# USB-A.net
KiCad netlist of a schematic drawn in EAGLE
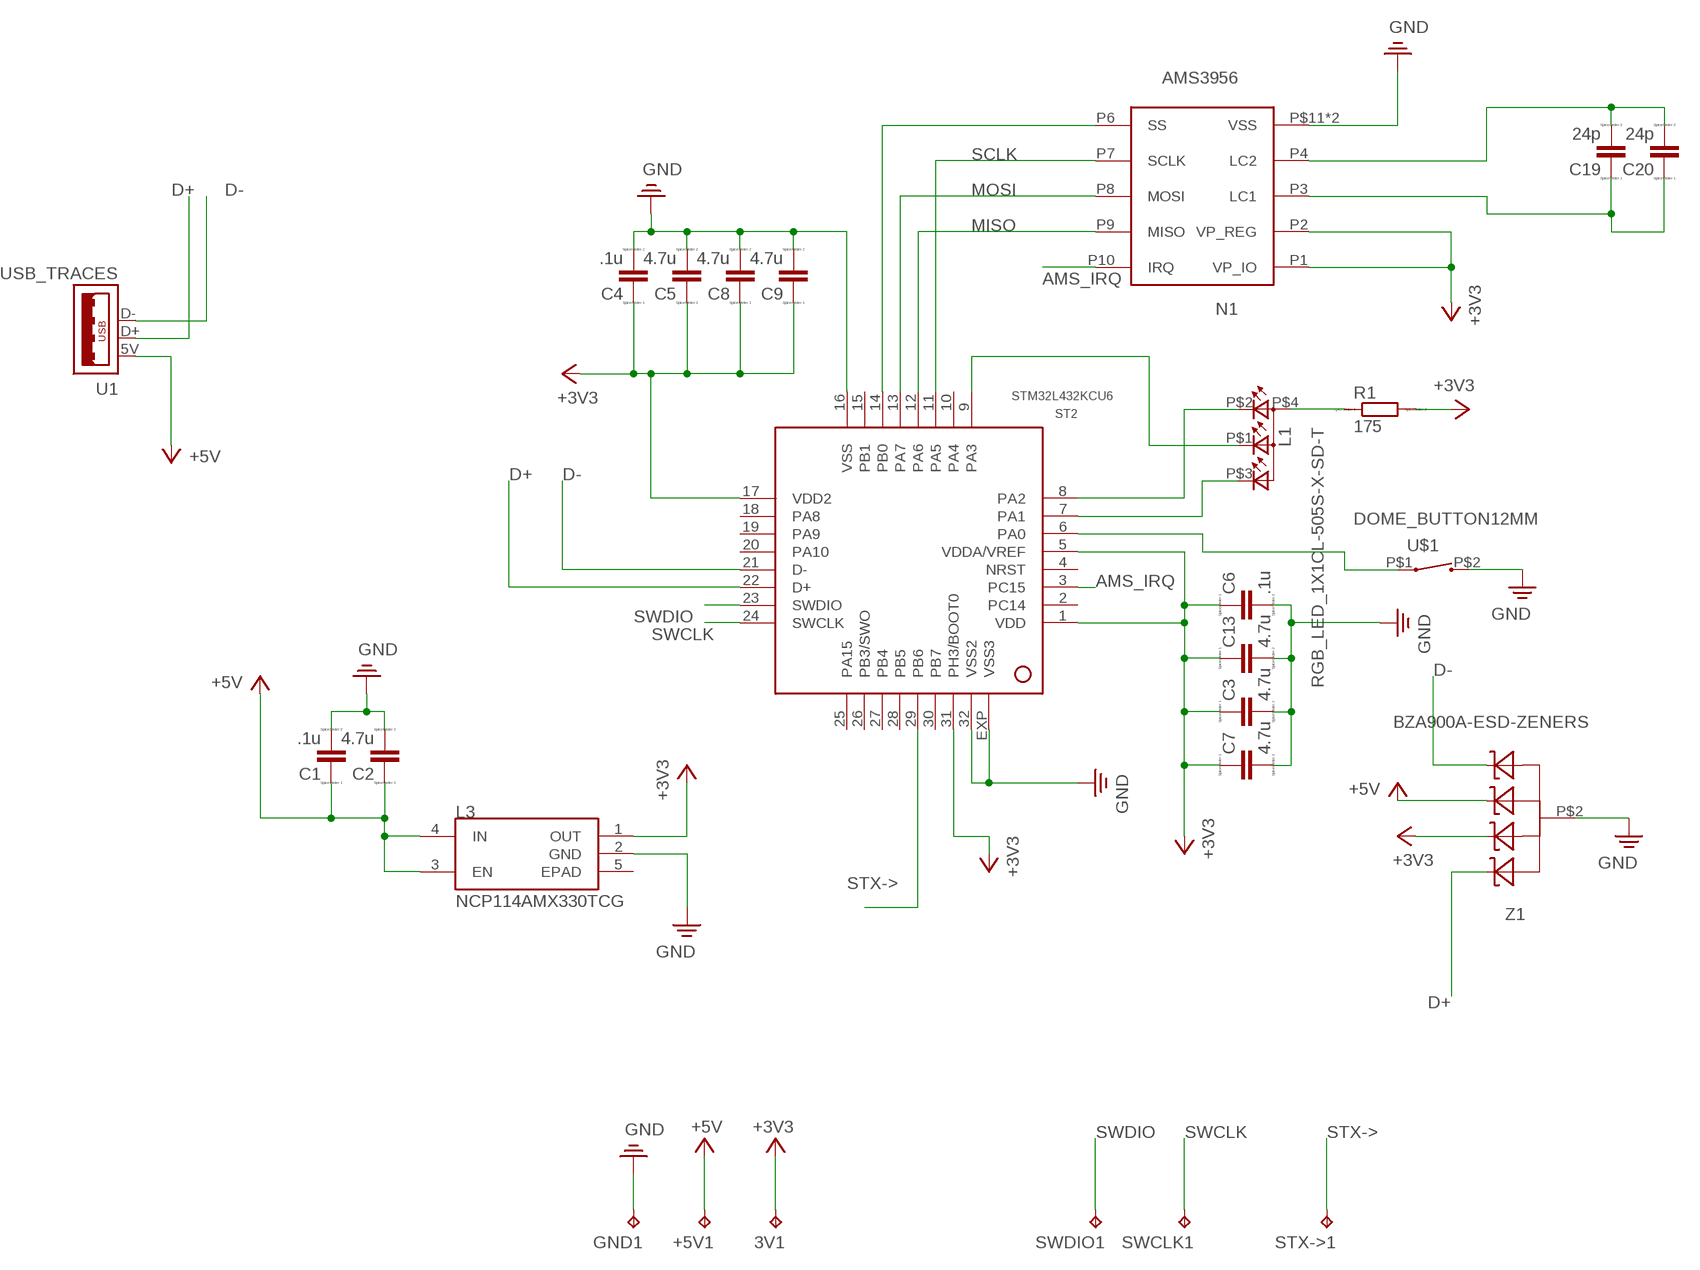
[diagram p0: schematic, sheet 1]

(export (version "E")
  (design (tool "Eeschema 10.0.6"))
  (components
    (comp (ref "+5V1")
      (value "TEST_POINT")
      (footprint "eagle-import:B1,27")
      (libsource (lib "eagle-import") (part "TEST_POINT"))
    )
    (comp (ref "3V1")
      (value "TEST_POINT")
      (footprint "eagle-import:B1,27")
      (libsource (lib "eagle-import") (part "TEST_POINT"))
    )
    (comp (ref "C1")
      (value ".1u")
      (footprint "eagle-import:C0402")
      (libsource (lib "eagle-import") (part "CAPACITOR"))
    )
    (comp (ref "C2")
      (value "4.7u")
      (footprint "eagle-import:C0402")
      (libsource (lib "eagle-import") (part "CAPACITOR"))
    )
    (comp (ref "C3")
      (value "4.7u")
      (footprint "eagle-import:C0402")
      (libsource (lib "eagle-import") (part "CAPACITOR"))
    )
    (comp (ref "C4")
      (value ".1u")
      (footprint "eagle-import:C0402")
      (libsource (lib "eagle-import") (part "CAPACITOR"))
    )
    (comp (ref "C5")
      (value "4.7u")
      (footprint "eagle-import:C0402")
      (libsource (lib "eagle-import") (part "CAPACITOR"))
    )
    (comp (ref "C6")
      (value ".1u")
      (footprint "eagle-import:C0402")
      (libsource (lib "eagle-import") (part "CAPACITOR"))
    )
    (comp (ref "C7")
      (value "4.7u")
      (footprint "eagle-import:C0402")
      (libsource (lib "eagle-import") (part "CAPACITOR"))
    )
    (comp (ref "C8")
      (value "4.7u")
      (footprint "eagle-import:C0402")
      (libsource (lib "eagle-import") (part "CAPACITOR"))
    )
    (comp (ref "C9")
      (value "4.7u")
      (footprint "eagle-import:C0402")
      (libsource (lib "eagle-import") (part "CAPACITOR"))
    )
    (comp (ref "C13")
      (value "4.7u")
      (footprint "eagle-import:C0402")
      (libsource (lib "eagle-import") (part "CAPACITOR"))
    )
    (comp (ref "C19")
      (value "24p")
      (footprint "eagle-import:C0402")
      (libsource (lib "eagle-import") (part "CAPACITOR"))
    )
    (comp (ref "C20")
      (value "24p")
      (footprint "eagle-import:C0402")
      (libsource (lib "eagle-import") (part "CAPACITOR"))
    )
    (comp (ref "GND1")
      (value "TEST_POINT")
      (footprint "eagle-import:B1,27")
      (libsource (lib "eagle-import") (part "TEST_POINT"))
    )
    (comp (ref "L1")
      (value "RGB_LED_1X1CL-505S-X-SD-T")
      (footprint "eagle-import:CL-505S-X-SD-T")
      (libsource (lib "eagle-import") (part "RGB_LED_1X1CL-505S-X-SD-T"))
    )
    (comp (ref "L3")
      (value "NCP114AMX330TCG")
      (footprint "eagle-import:REG_NCP114AMX330TCG")
      (fields (field (name "MF") "ON Semiconductor"))
      (libsource (lib "eagle-import") (part "NCP114AMX330TCG"))
    )
    (comp (ref "N1")
      (value "AMS3956")
      (footprint "eagle-import:MLPD3X3")
      (libsource (lib "eagle-import") (part "AMS3956"))
    )
    (comp (ref "R1")
      (value "175")
      (footprint "eagle-import:R0402")
      (libsource (lib "eagle-import") (part "RESISTOR"))
    )
    (comp (ref "ST2")
      (value "STM32L432KCU6")
      (footprint "eagle-import:QFN32")
      (libsource (lib "eagle-import") (part "STM32L432KCU6"))
    )
    (comp (ref "STX->1")
      (value "TEST_POINT")
      (footprint "eagle-import:B1,27")
      (libsource (lib "eagle-import") (part "TEST_POINT"))
    )
    (comp (ref "SWCLK1")
      (value "TEST_POINT")
      (footprint "eagle-import:B1,27")
      (libsource (lib "eagle-import") (part "TEST_POINT"))
    )
    (comp (ref "SWDIO1")
      (value "TEST_POINT")
      (footprint "eagle-import:B1,27")
      (libsource (lib "eagle-import") (part "TEST_POINT"))
    )
    (comp (ref "U$1")
      (value "DOME_BUTTON12MM")
      (footprint "eagle-import:DOME-BL-12MM")
      (libsource (lib "eagle-import") (part "DOME_BUTTON12MM"))
    )
    (comp (ref "U1")
      (value "USB_TRACES")
      (footprint "eagle-import:USB_TRACES")
      (libsource (lib "eagle-import") (part "USB_TRACES"))
    )
    (comp (ref "Z1")
      (value "BZA900A-ESD-ZENERS")
      (footprint "eagle-import:BZA900A")
      (libsource (lib "eagle-import") (part "BZA900A-ESD-ZENERS"))
    )
  )
  (nets
    (net (code "1") (name "+3V3") (class "Default")
      (node (ref "3V1") (pin "TP") (pinfunction "TP_TP") (pintype "input"))
      (node (ref "C13") (pin "1") (pinfunction "1_1") (pintype "passive"))
      (node (ref "C3") (pin "1") (pinfunction "1_1") (pintype "passive"))
      (node (ref "C4") (pin "1") (pinfunction "1_1") (pintype "passive"))
      (node (ref "C5") (pin "1") (pinfunction "1_1") (pintype "passive"))
      (node (ref "C6") (pin "1") (pinfunction "1_1") (pintype "passive"))
      (node (ref "C7") (pin "1") (pinfunction "1_1") (pintype "passive"))
      (node (ref "C8") (pin "1") (pinfunction "1_1") (pintype "passive"))
      (node (ref "C9") (pin "1") (pinfunction "1_1") (pintype "passive"))
      (node (ref "L3") (pin "1") (pinfunction "OUT_1") (pintype "output"))
      (node (ref "N1") (pin "P1") (pinfunction "VP_IO_P1") (pintype "bidirectional"))
      (node (ref "N1") (pin "P2") (pinfunction "VP_REG_P2") (pintype "bidirectional"))
      (node (ref "R1") (pin "2") (pinfunction "2_2") (pintype "passive"))
      (node (ref "ST2") (pin "1") (pinfunction "VDD_1") (pintype "bidirectional"))
      (node (ref "ST2") (pin "17") (pinfunction "VDD2_17") (pintype "bidirectional"))
      (node (ref "ST2") (pin "31") (pinfunction "PH3/BOOT0_31") (pintype "bidirectional"))
      (node (ref "ST2") (pin "5") (pinfunction "VDDA/VREF_5") (pintype "bidirectional"))
      (node (ref "Z1") (pin "P$5") (pinfunction "C1_P$5") (pintype "passive"))
    )
    (net (code "2") (name "+5V") (class "Default")
      (node (ref "+5V1") (pin "TP") (pinfunction "TP_TP") (pintype "input"))
      (node (ref "C1") (pin "1") (pinfunction "1_1") (pintype "passive"))
      (node (ref "C2") (pin "1") (pinfunction "1_1") (pintype "passive"))
      (node (ref "L3") (pin "3") (pinfunction "EN_3") (pintype "input"))
      (node (ref "L3") (pin "4") (pinfunction "IN_4") (pintype "input"))
      (node (ref "U1") (pin "5V") (pinfunction "1_5V") (pintype "passive"))
      (node (ref "Z1") (pin "P$1") (pinfunction "C_P$1") (pintype "passive"))
    )
    (net (code "3") (name "/AMS_IRQ") (class "Default")
      (node (ref "N1") (pin "P10") (pinfunction "IRQ_P10") (pintype "bidirectional"))
      (node (ref "ST2") (pin "3") (pinfunction "PC15_3") (pintype "bidirectional"))
    )
    (net (code "4") (name "/D+") (class "Default")
      (node (ref "ST2") (pin "22") (pinfunction "D+_22") (pintype "bidirectional"))
      (node (ref "U1") (pin "D+") (pinfunction "2_D+") (pintype "passive"))
      (node (ref "Z1") (pin "P$3") (pinfunction "C3_P$3") (pintype "passive"))
    )
    (net (code "5") (name "/D-") (class "Default")
      (node (ref "ST2") (pin "21") (pinfunction "D-_21") (pintype "bidirectional"))
      (node (ref "U1") (pin "D-") (pinfunction "3_D-") (pintype "passive"))
      (node (ref "Z1") (pin "P$4") (pinfunction "C2_P$4") (pintype "passive"))
    )
    (net (code "6") (name "/MISO") (class "Default")
      (node (ref "N1") (pin "P9") (pinfunction "MISO_P9") (pintype "bidirectional"))
      (node (ref "ST2") (pin "12") (pinfunction "PA6_12") (pintype "bidirectional"))
    )
    (net (code "7") (name "/MOSI") (class "Default")
      (node (ref "N1") (pin "P8") (pinfunction "MOSI_P8") (pintype "bidirectional"))
      (node (ref "ST2") (pin "13") (pinfunction "PA7_13") (pintype "bidirectional"))
    )
    (net (code "8") (name "/SCLK") (class "Default")
      (node (ref "N1") (pin "P7") (pinfunction "SCLK_P7") (pintype "bidirectional"))
      (node (ref "ST2") (pin "11") (pinfunction "PA5_11") (pintype "bidirectional"))
    )
    (net (code "9") (name "/STX->") (class "Default")
      (node (ref "ST2") (pin "29") (pinfunction "PB6_29") (pintype "bidirectional"))
      (node (ref "STX->1") (pin "TP") (pinfunction "TP_TP") (pintype "input"))
    )
    (net (code "10") (name "/SWCLK") (class "Default")
      (node (ref "ST2") (pin "24") (pinfunction "SWCLK_24") (pintype "bidirectional"))
      (node (ref "SWCLK1") (pin "TP") (pinfunction "TP_TP") (pintype "input"))
    )
    (net (code "11") (name "/SWDIO") (class "Default")
      (node (ref "ST2") (pin "23") (pinfunction "SWDIO_23") (pintype "bidirectional"))
      (node (ref "SWDIO1") (pin "TP") (pinfunction "TP_TP") (pintype "input"))
    )
    (net (code "12") (name "GND") (class "Default")
      (node (ref "C1") (pin "2") (pinfunction "2_2") (pintype "passive"))
      (node (ref "C13") (pin "2") (pinfunction "2_2") (pintype "passive"))
      (node (ref "C2") (pin "2") (pinfunction "2_2") (pintype "passive"))
      (node (ref "C3") (pin "2") (pinfunction "2_2") (pintype "passive"))
      (node (ref "C4") (pin "2") (pinfunction "2_2") (pintype "passive"))
      (node (ref "C5") (pin "2") (pinfunction "2_2") (pintype "passive"))
      (node (ref "C6") (pin "2") (pinfunction "2_2") (pintype "passive"))
      (node (ref "C7") (pin "2") (pinfunction "2_2") (pintype "passive"))
      (node (ref "C8") (pin "2") (pinfunction "2_2") (pintype "passive"))
      (node (ref "C9") (pin "2") (pinfunction "2_2") (pintype "passive"))
      (node (ref "GND1") (pin "TP") (pinfunction "TP_TP") (pintype "input"))
      (node (ref "L3") (pin "2") (pinfunction "GND_2") (pintype "power_in"))
      (node (ref "N1") (pin "P$11") (pinfunction "VSS_P$11") (pintype "bidirectional"))
      (node (ref "N1") (pin "P5") (pinfunction "VSS_P5") (pintype "bidirectional"))
      (node (ref "ST2") (pin "16") (pinfunction "VSS_16") (pintype "bidirectional"))
      (node (ref "ST2") (pin "32") (pinfunction "VSS2_32") (pintype "bidirectional"))
      (node (ref "ST2") (pin "EXP") (pinfunction "VSS3_EXP") (pintype "bidirectional"))
      (node (ref "U$1") (pin "P$2") (pinfunction "2_P$2") (pintype "passive"))
      (node (ref "Z1") (pin "P$2") (pinfunction "P$1_P$2") (pintype "bidirectional"))
    )
    (net (code "13") (name "Net-(L1-A2)") (class "Default")
      (node (ref "L1") (pin "P$4") (pinfunction "A2_P$4") (pintype "passive"))
      (node (ref "R1") (pin "1") (pinfunction "1_1") (pintype "passive"))
    )
    (net (code "14") (name "Net-(L1-CBLUE)") (class "Default")
      (node (ref "L1") (pin "P$1") (pinfunction "CBLUE_P$1") (pintype "passive"))
      (node (ref "ST2") (pin "9") (pinfunction "PA3_9") (pintype "bidirectional"))
    )
    (net (code "15") (name "Net-(L1-CGREEN)") (class "Default")
      (node (ref "L1") (pin "P$3") (pinfunction "CGREEN_P$3") (pintype "passive"))
      (node (ref "ST2") (pin "7") (pinfunction "PA1_7") (pintype "bidirectional"))
    )
    (net (code "16") (name "Net-(L1-CRED)") (class "Default")
      (node (ref "L1") (pin "P$2") (pinfunction "CRED_P$2") (pintype "passive"))
      (node (ref "ST2") (pin "8") (pinfunction "PA2_8") (pintype "bidirectional"))
    )
    (net (code "17") (name "Net-(N1-LC1)") (class "Default")
      (node (ref "C19") (pin "1") (pinfunction "1_1") (pintype "passive"))
      (node (ref "C20") (pin "1") (pinfunction "1_1") (pintype "passive"))
      (node (ref "N1") (pin "P3") (pinfunction "LC1_P3") (pintype "bidirectional"))
    )
    (net (code "18") (name "Net-(N1-LC2)") (class "Default")
      (node (ref "C19") (pin "2") (pinfunction "2_2") (pintype "passive"))
      (node (ref "C20") (pin "2") (pinfunction "2_2") (pintype "passive"))
      (node (ref "N1") (pin "P4") (pinfunction "LC2_P4") (pintype "bidirectional"))
    )
    (net (code "19") (name "Net-(N1-SS)") (class "Default")
      (node (ref "N1") (pin "P6") (pinfunction "SS_P6") (pintype "bidirectional"))
      (node (ref "ST2") (pin "14") (pinfunction "PB0_14") (pintype "bidirectional"))
    )
    (net (code "20") (name "Net-(ST2-PA0)") (class "Default")
      (node (ref "ST2") (pin "6") (pinfunction "PA0_6") (pintype "bidirectional"))
      (node (ref "U$1") (pin "P$1") (pinfunction "1_P$1") (pintype "passive"))
    )
    (net (code "21") (name "unconnected-(L3-EPAD-Pad5)") (class "Default")
      (node (ref "L3") (pin "5") (pinfunction "EPAD_5") (pintype "passive"))
    )
    (net (code "22") (name "unconnected-(ST2-NRST-Pad4)") (class "Default")
      (node (ref "ST2") (pin "4") (pinfunction "NRST_4") (pintype "bidirectional"))
    )
    (net (code "23") (name "unconnected-(ST2-PA4-Pad10)") (class "Default")
      (node (ref "ST2") (pin "10") (pinfunction "PA4_10") (pintype "bidirectional"))
    )
    (net (code "24") (name "unconnected-(ST2-PA8-Pad18)") (class "Default")
      (node (ref "ST2") (pin "18") (pinfunction "PA8_18") (pintype "bidirectional"))
    )
    (net (code "25") (name "unconnected-(ST2-PA9-Pad19)") (class "Default")
      (node (ref "ST2") (pin "19") (pinfunction "PA9_19") (pintype "bidirectional"))
    )
    (net (code "26") (name "unconnected-(ST2-PA10-Pad20)") (class "Default")
      (node (ref "ST2") (pin "20") (pinfunction "PA10_20") (pintype "bidirectional"))
    )
    (net (code "27") (name "unconnected-(ST2-PA15-Pad25)") (class "Default")
      (node (ref "ST2") (pin "25") (pinfunction "PA15_25") (pintype "bidirectional"))
    )
    (net (code "28") (name "unconnected-(ST2-PB1-Pad15)") (class "Default")
      (node (ref "ST2") (pin "15") (pinfunction "PB1_15") (pintype "bidirectional"))
    )
    (net (code "29") (name "unconnected-(ST2-PB3{slash}SWO-Pad26)") (class "Default")
      (node (ref "ST2") (pin "26") (pinfunction "PB3/SWO_26") (pintype "bidirectional"))
    )
    (net (code "30") (name "unconnected-(ST2-PB4-Pad27)") (class "Default")
      (node (ref "ST2") (pin "27") (pinfunction "PB4_27") (pintype "bidirectional"))
    )
    (net (code "31") (name "unconnected-(ST2-PB5-Pad28)") (class "Default")
      (node (ref "ST2") (pin "28") (pinfunction "PB5_28") (pintype "bidirectional"))
    )
    (net (code "32") (name "unconnected-(ST2-PB7-Pad30)") (class "Default")
      (node (ref "ST2") (pin "30") (pinfunction "PB7_30") (pintype "bidirectional"))
    )
    (net (code "33") (name "unconnected-(ST2-PC14-Pad2)") (class "Default")
      (node (ref "ST2") (pin "2") (pinfunction "PC14_2") (pintype "bidirectional"))
    )
  )
)
